# valves_card.net
KiCad netlist of a schematic drawn in EAGLE
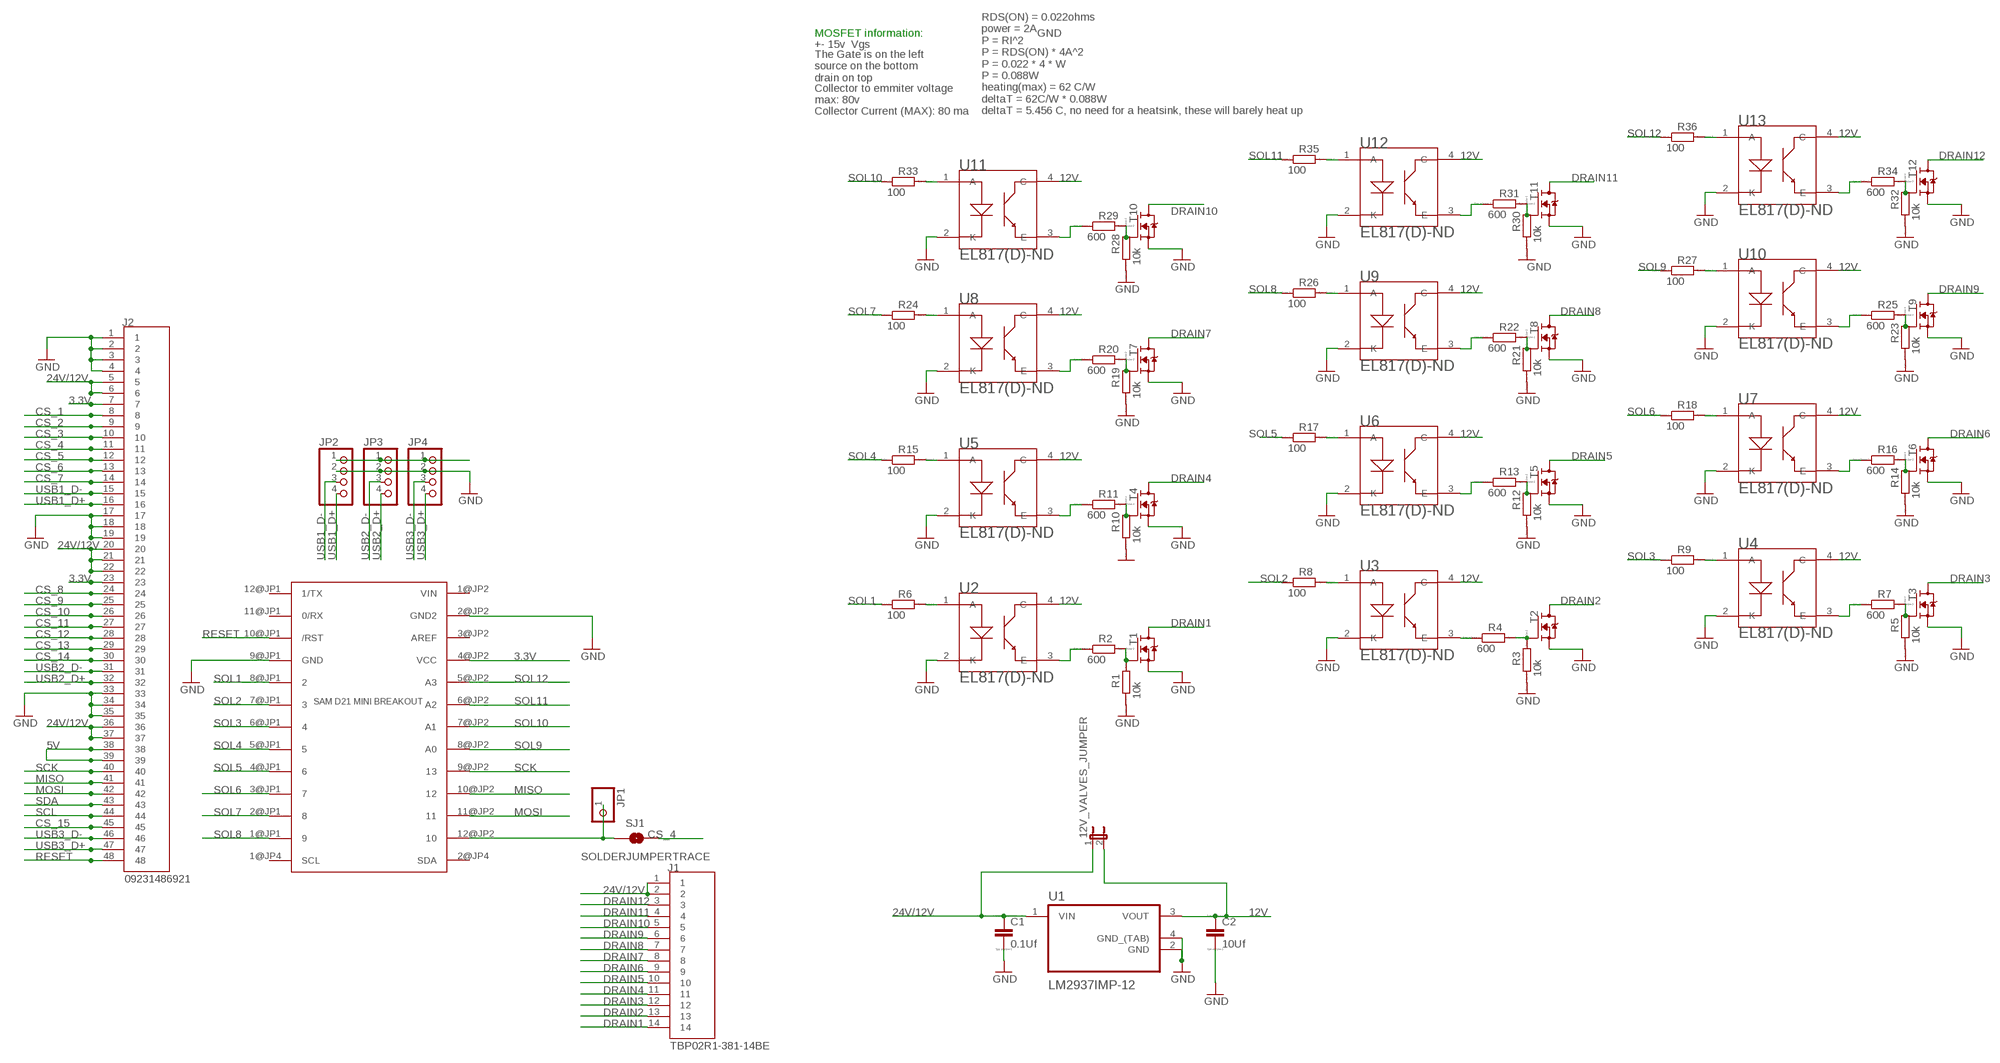
[diagram p0: schematic, sheet 1]

(export (version "E")
  (design (tool "Eeschema 10.0.6"))
  (components
    (comp (ref "12V_VALVES_JUMPER")
      (value "JUMPER-2SMD-NO")
      (footprint "eagle-import:SJ_2S-NO")
      (libsource (lib "eagle-import") (part "JUMPER-2SMD-NO"))
    )
    (comp (ref "C1")
      (value "0.1Uf")
      (footprint "eagle-import:C0805")
      (libsource (lib "eagle-import") (part "C"))
    )
    (comp (ref "C2")
      (value "10Uf")
      (footprint "eagle-import:C1206")
      (libsource (lib "eagle-import") (part "CC1206"))
    )
    (comp (ref "J1")
      (value "TBP02R1-381-14BE")
      (footprint "eagle-import:CUI_TBP02R1-381-14BE")
      (fields (field (name "MF") "CUI Devices"))
      (libsource (lib "eagle-import") (part "TBP02R1-381-14BE"))
    )
    (comp (ref "J2")
      (value "09231486921")
      (footprint "eagle-import:HARTING_09231486921")
      (fields (field (name "MF") "HARTING"))
      (libsource (lib "eagle-import") (part "09231486921"))
    )
    (comp (ref "JP1")
      (value "PINHD-1X1")
      (footprint "eagle-import:1X01")
      (libsource (lib "eagle-import") (part "PINHD-1X1"))
    )
    (comp (ref "JP2")
      (value "PINHD-1X4")
      (footprint "eagle-import:1X04")
      (libsource (lib "eagle-import") (part "PINHD-1X4"))
    )
    (comp (ref "JP3")
      (value "PINHD-1X4")
      (footprint "eagle-import:1X04")
      (libsource (lib "eagle-import") (part "PINHD-1X4"))
    )
    (comp (ref "JP4")
      (value "PINHD-1X4")
      (footprint "eagle-import:1X04")
      (libsource (lib "eagle-import") (part "PINHD-1X4"))
    )
    (comp (ref "M2")
      (value "SAM_D21_MINI_BREAKOUT")
      (footprint "eagle-import:JP1_SPARKFUN-SAMD21-MINI-BREAKOUT-V10")
      (libsource (lib "eagle-import") (part "SAM_D21_MINI_BREAKOUT"))
    )
    (comp (ref "R1")
      (value "10k")
      (footprint "eagle-import:R0805")
      (libsource (lib "eagle-import") (part "R"))
    )
    (comp (ref "R2")
      (value "600")
      (footprint "eagle-import:R0805")
      (libsource (lib "eagle-import") (part "R"))
    )
    (comp (ref "R3")
      (value "10k")
      (footprint "eagle-import:R0805")
      (libsource (lib "eagle-import") (part "R"))
    )
    (comp (ref "R4")
      (value "600")
      (footprint "eagle-import:R0805")
      (libsource (lib "eagle-import") (part "R"))
    )
    (comp (ref "R5")
      (value "10k")
      (footprint "eagle-import:R0805")
      (libsource (lib "eagle-import") (part "R"))
    )
    (comp (ref "R6")
      (value "100")
      (footprint "eagle-import:R0805")
      (libsource (lib "eagle-import") (part "R"))
    )
    (comp (ref "R7")
      (value "600")
      (footprint "eagle-import:R0805")
      (libsource (lib "eagle-import") (part "R"))
    )
    (comp (ref "R8")
      (value "100")
      (footprint "eagle-import:R0805")
      (libsource (lib "eagle-import") (part "R"))
    )
    (comp (ref "R9")
      (value "100")
      (footprint "eagle-import:R0805")
      (libsource (lib "eagle-import") (part "R"))
    )
    (comp (ref "R10")
      (value "10k")
      (footprint "eagle-import:R0805")
      (libsource (lib "eagle-import") (part "R"))
    )
    (comp (ref "R11")
      (value "600")
      (footprint "eagle-import:R0805")
      (libsource (lib "eagle-import") (part "R"))
    )
    (comp (ref "R12")
      (value "10k")
      (footprint "eagle-import:R0805")
      (libsource (lib "eagle-import") (part "R"))
    )
    (comp (ref "R13")
      (value "600")
      (footprint "eagle-import:R0805")
      (libsource (lib "eagle-import") (part "R"))
    )
    (comp (ref "R14")
      (value "10k")
      (footprint "eagle-import:R0805")
      (libsource (lib "eagle-import") (part "R"))
    )
    (comp (ref "R15")
      (value "100")
      (footprint "eagle-import:R0805")
      (libsource (lib "eagle-import") (part "R"))
    )
    (comp (ref "R16")
      (value "600")
      (footprint "eagle-import:R0805")
      (libsource (lib "eagle-import") (part "R"))
    )
    (comp (ref "R17")
      (value "100")
      (footprint "eagle-import:R0805")
      (libsource (lib "eagle-import") (part "R"))
    )
    (comp (ref "R18")
      (value "100")
      (footprint "eagle-import:R0805")
      (libsource (lib "eagle-import") (part "R"))
    )
    (comp (ref "R19")
      (value "10k")
      (footprint "eagle-import:R0805")
      (libsource (lib "eagle-import") (part "R"))
    )
    (comp (ref "R20")
      (value "600")
      (footprint "eagle-import:R0805")
      (libsource (lib "eagle-import") (part "R"))
    )
    (comp (ref "R21")
      (value "10k")
      (footprint "eagle-import:R0805")
      (libsource (lib "eagle-import") (part "R"))
    )
    (comp (ref "R22")
      (value "600")
      (footprint "eagle-import:R0805")
      (libsource (lib "eagle-import") (part "R"))
    )
    (comp (ref "R23")
      (value "10k")
      (footprint "eagle-import:R0805")
      (libsource (lib "eagle-import") (part "R"))
    )
    (comp (ref "R24")
      (value "100")
      (footprint "eagle-import:R0805")
      (libsource (lib "eagle-import") (part "R"))
    )
    (comp (ref "R25")
      (value "600")
      (footprint "eagle-import:R0805")
      (libsource (lib "eagle-import") (part "R"))
    )
    (comp (ref "R26")
      (value "100")
      (footprint "eagle-import:R0805")
      (libsource (lib "eagle-import") (part "R"))
    )
    (comp (ref "R27")
      (value "100")
      (footprint "eagle-import:R0805")
      (libsource (lib "eagle-import") (part "R"))
    )
    (comp (ref "R28")
      (value "10k")
      (footprint "eagle-import:R0805")
      (libsource (lib "eagle-import") (part "R"))
    )
    (comp (ref "R29")
      (value "600")
      (footprint "eagle-import:R0805")
      (libsource (lib "eagle-import") (part "R"))
    )
    (comp (ref "R30")
      (value "10k")
      (footprint "eagle-import:R0805")
      (libsource (lib "eagle-import") (part "R"))
    )
    (comp (ref "R31")
      (value "600")
      (footprint "eagle-import:R0805")
      (libsource (lib "eagle-import") (part "R"))
    )
    (comp (ref "R32")
      (value "10k")
      (footprint "eagle-import:R0805")
      (libsource (lib "eagle-import") (part "R"))
    )
    (comp (ref "R33")
      (value "100")
      (footprint "eagle-import:R0805")
      (libsource (lib "eagle-import") (part "R"))
    )
    (comp (ref "R34")
      (value "600")
      (footprint "eagle-import:R0805")
      (libsource (lib "eagle-import") (part "R"))
    )
    (comp (ref "R35")
      (value "100")
      (footprint "eagle-import:R0805")
      (libsource (lib "eagle-import") (part "R"))
    )
    (comp (ref "R36")
      (value "100")
      (footprint "eagle-import:R0805")
      (libsource (lib "eagle-import") (part "R"))
    )
    (comp (ref "SJ1")
      (value "SOLDERJUMPERTRACE")
      (footprint "eagle-import:SJ_2S-TRACE")
      (libsource (lib "eagle-import") (part "SOLDERJUMPERTRACE"))
    )
    (comp (ref "T1")
      (value "IRLZ44NSTRLPBF")
      (footprint "eagle-import:DPAK_TO252")
      (libsource (lib "eagle-import") (part "BUK9214-30A-118-DPAK"))
    )
    (comp (ref "T2")
      (value "IRLZ44NSTRLPBF")
      (footprint "eagle-import:DPAK_TO252")
      (libsource (lib "eagle-import") (part "BUK9214-30A-118-DPAK"))
    )
    (comp (ref "T3")
      (value "IRLZ44NSTRLPBF")
      (footprint "eagle-import:DPAK_TO252")
      (libsource (lib "eagle-import") (part "BUK9214-30A-118-DPAK"))
    )
    (comp (ref "T4")
      (value "IRLZ44NSTRLPBF")
      (footprint "eagle-import:DPAK_TO252")
      (libsource (lib "eagle-import") (part "BUK9214-30A-118-DPAK"))
    )
    (comp (ref "T5")
      (value "IRLZ44NSTRLPBF")
      (footprint "eagle-import:DPAK_TO252")
      (libsource (lib "eagle-import") (part "BUK9214-30A-118-DPAK"))
    )
    (comp (ref "T6")
      (value "IRLZ44NSTRLPBF")
      (footprint "eagle-import:DPAK_TO252")
      (libsource (lib "eagle-import") (part "BUK9214-30A-118-DPAK"))
    )
    (comp (ref "T7")
      (value "IRLZ44NSTRLPBF")
      (footprint "eagle-import:DPAK_TO252")
      (libsource (lib "eagle-import") (part "BUK9214-30A-118-DPAK"))
    )
    (comp (ref "T8")
      (value "IRLZ44NSTRLPBF")
      (footprint "eagle-import:DPAK_TO252")
      (libsource (lib "eagle-import") (part "BUK9214-30A-118-DPAK"))
    )
    (comp (ref "T9")
      (value "IRLZ44NSTRLPBF")
      (footprint "eagle-import:DPAK_TO252")
      (libsource (lib "eagle-import") (part "BUK9214-30A-118-DPAK"))
    )
    (comp (ref "T10")
      (value "IRLZ44NSTRLPBF")
      (footprint "eagle-import:DPAK_TO252")
      (libsource (lib "eagle-import") (part "BUK9214-30A-118-DPAK"))
    )
    (comp (ref "T11")
      (value "IRLZ44NSTRLPBF")
      (footprint "eagle-import:DPAK_TO252")
      (libsource (lib "eagle-import") (part "BUK9214-30A-118-DPAK"))
    )
    (comp (ref "T12")
      (value "IRLZ44NSTRLPBF")
      (footprint "eagle-import:DPAK_TO252")
      (libsource (lib "eagle-import") (part "BUK9214-30A-118-DPAK"))
    )
    (comp (ref "U1")
      (value "LM2937IMP-12")
      (footprint "eagle-import:SOT230P700X180-4N")
      (fields (field (name "MF") "Texas Instruments") (field (name "MP") "LM2937IMP-10"))
      (libsource (lib "eagle-import") (part "LM2937IMP-10"))
    )
    (comp (ref "U2")
      (value "EL817(D)-ND")
      (footprint "eagle-import:DIP762W25P254L650H453Q4B")
      (fields (field (name "MF") "Everlight") (field (name "MP") "EL817(C)") (field (name "MP_1") "OR-815"))
      (libsource (lib "eagle-import") (part "EL817C"))
    )
    (comp (ref "U3")
      (value "EL817(D)-ND")
      (footprint "eagle-import:DIP762W25P254L650H453Q4B")
      (fields (field (name "MF") "Everlight") (field (name "MP") "EL817(C)") (field (name "MP_1") "OR-815"))
      (libsource (lib "eagle-import") (part "EL817C"))
    )
    (comp (ref "U4")
      (value "EL817(D)-ND")
      (footprint "eagle-import:DIP762W25P254L650H453Q4B")
      (fields (field (name "MF") "Everlight") (field (name "MP") "EL817(C)"))
      (libsource (lib "eagle-import") (part "EL817C"))
    )
    (comp (ref "U5")
      (value "EL817(D)-ND")
      (footprint "eagle-import:DIP762W25P254L650H453Q4B")
      (fields (field (name "MF") "Everlight") (field (name "MP") "EL817(C)"))
      (libsource (lib "eagle-import") (part "EL817C"))
    )
    (comp (ref "U6")
      (value "EL817(D)-ND")
      (footprint "eagle-import:DIP762W25P254L650H453Q4B")
      (fields (field (name "MF") "Everlight") (field (name "MP") "EL817(C)"))
      (libsource (lib "eagle-import") (part "EL817C"))
    )
    (comp (ref "U7")
      (value "EL817(D)-ND")
      (footprint "eagle-import:DIP762W25P254L650H453Q4B")
      (fields (field (name "MF") "Everlight") (field (name "MP") "EL817(C)"))
      (libsource (lib "eagle-import") (part "EL817C"))
    )
    (comp (ref "U8")
      (value "EL817(D)-ND")
      (footprint "eagle-import:DIP762W25P254L650H453Q4B")
      (fields (field (name "MF") "Everlight") (field (name "MP") "EL817(C)"))
      (libsource (lib "eagle-import") (part "EL817C"))
    )
    (comp (ref "U9")
      (value "EL817(D)-ND")
      (footprint "eagle-import:DIP762W25P254L650H453Q4B")
      (fields (field (name "MF") "Everlight") (field (name "MP") "EL817(C)"))
      (libsource (lib "eagle-import") (part "EL817C"))
    )
    (comp (ref "U10")
      (value "EL817(D)-ND")
      (footprint "eagle-import:DIP762W25P254L650H453Q4B")
      (fields (field (name "MF") "Everlight") (field (name "MP") "EL817(C)"))
      (libsource (lib "eagle-import") (part "EL817C"))
    )
    (comp (ref "U11")
      (value "EL817(D)-ND")
      (footprint "eagle-import:DIP762W25P254L650H453Q4B")
      (fields (field (name "MF") "Everlight") (field (name "MP") "EL817(C)"))
      (libsource (lib "eagle-import") (part "EL817C"))
    )
    (comp (ref "U12")
      (value "EL817(D)-ND")
      (footprint "eagle-import:DIP762W25P254L650H453Q4B")
      (fields (field (name "MF") "Everlight") (field (name "MP") "EL817(C)"))
      (libsource (lib "eagle-import") (part "EL817C"))
    )
    (comp (ref "U13")
      (value "EL817(D)-ND")
      (footprint "eagle-import:DIP762W25P254L650H453Q4B")
      (fields (field (name "MF") "Everlight") (field (name "MP") "EL817(C)"))
      (libsource (lib "eagle-import") (part "EL817C"))
    )
  )
  (nets
    (net (code "1") (name "/3.3V") (class "Default")
      (node (ref "J2") (pin "23") (pinfunction "23_23") (pintype "passive"))
      (node (ref "J2") (pin "7") (pinfunction "7_7") (pintype "passive"))
      (node (ref "M2") (pin "4@JP2") (pinfunction "VCC_4@JP2") (pintype "power_in"))
    )
    (net (code "2") (name "/5V") (class "Default")
      (node (ref "J2") (pin "38") (pinfunction "38_38") (pintype "passive"))
      (node (ref "J2") (pin "39") (pinfunction "39_39") (pintype "passive"))
      (node (ref "JP2") (pin "1") (pinfunction "1_1") (pintype "passive"))
      (node (ref "JP3") (pin "1") (pinfunction "1_1") (pintype "passive"))
      (node (ref "JP4") (pin "1") (pinfunction "1_1") (pintype "passive"))
    )
    (net (code "3") (name "/12V") (class "Default")
      (node (ref "12V_VALVES_JUMPER") (pin "2") (pinfunction "2_2") (pintype "passive"))
      (node (ref "C2") (pin "1") (pinfunction "1_1") (pintype "passive"))
      (node (ref "U1") (pin "3") (pinfunction "VOUT_3") (pintype "output"))
      (node (ref "U10") (pin "4") (pinfunction "C_4") (pintype "passive"))
      (node (ref "U11") (pin "4") (pinfunction "C_4") (pintype "passive"))
      (node (ref "U12") (pin "4") (pinfunction "C_4") (pintype "passive"))
      (node (ref "U13") (pin "4") (pinfunction "C_4") (pintype "passive"))
      (node (ref "U2") (pin "4") (pinfunction "C_4") (pintype "passive"))
      (node (ref "U3") (pin "4") (pinfunction "C_4") (pintype "passive"))
      (node (ref "U4") (pin "4") (pinfunction "C_4") (pintype "passive"))
      (node (ref "U5") (pin "4") (pinfunction "C_4") (pintype "passive"))
      (node (ref "U6") (pin "4") (pinfunction "C_4") (pintype "passive"))
      (node (ref "U7") (pin "4") (pinfunction "C_4") (pintype "passive"))
      (node (ref "U8") (pin "4") (pinfunction "C_4") (pintype "passive"))
      (node (ref "U9") (pin "4") (pinfunction "C_4") (pintype "passive"))
    )
    (net (code "4") (name "/24V{slash}12V") (class "Default")
      (node (ref "12V_VALVES_JUMPER") (pin "1") (pinfunction "1_1") (pintype "passive"))
      (node (ref "C1") (pin "1") (pinfunction "1_1") (pintype "passive"))
      (node (ref "J1") (pin "1") (pinfunction "1_1") (pintype "passive"))
      (node (ref "J1") (pin "2") (pinfunction "2_2") (pintype "passive"))
      (node (ref "J2") (pin "20") (pinfunction "20_20") (pintype "passive"))
      (node (ref "J2") (pin "21") (pinfunction "21_21") (pintype "passive"))
      (node (ref "J2") (pin "22") (pinfunction "22_22") (pintype "passive"))
      (node (ref "J2") (pin "36") (pinfunction "36_36") (pintype "passive"))
      (node (ref "J2") (pin "37") (pinfunction "37_37") (pintype "passive"))
      (node (ref "J2") (pin "5") (pinfunction "5_5") (pintype "passive"))
      (node (ref "J2") (pin "6") (pinfunction "6_6") (pintype "passive"))
      (node (ref "U1") (pin "1") (pinfunction "VIN_1") (pintype "input"))
    )
    (net (code "5") (name "/AREF") (class "Default")
      (node (ref "M2") (pin "3@JP2") (pinfunction "AREF_3@JP2") (pintype "power_in"))
    )
    (net (code "6") (name "/CS_1") (class "Default")
      (node (ref "J2") (pin "8") (pinfunction "8_8") (pintype "passive"))
    )
    (net (code "7") (name "/CS_2") (class "Default")
      (node (ref "J2") (pin "9") (pinfunction "9_9") (pintype "passive"))
    )
    (net (code "8") (name "/CS_3") (class "Default")
      (node (ref "J2") (pin "10") (pinfunction "10_10") (pintype "passive"))
    )
    (net (code "9") (name "/CS_4") (class "Default")
      (node (ref "J2") (pin "11") (pinfunction "11_11") (pintype "passive"))
      (node (ref "SJ1") (pin "2") (pinfunction "2_2") (pintype "passive"))
    )
    (net (code "10") (name "/CS_5") (class "Default")
      (node (ref "J2") (pin "12") (pinfunction "12_12") (pintype "passive"))
    )
    (net (code "11") (name "/CS_6") (class "Default")
      (node (ref "J2") (pin "13") (pinfunction "13_13") (pintype "passive"))
    )
    (net (code "12") (name "/CS_7") (class "Default")
      (node (ref "J2") (pin "14") (pinfunction "14_14") (pintype "passive"))
    )
    (net (code "13") (name "/CS_8") (class "Default")
      (node (ref "J2") (pin "24") (pinfunction "24_24") (pintype "passive"))
    )
    (net (code "14") (name "/CS_9") (class "Default")
      (node (ref "J2") (pin "25") (pinfunction "25_25") (pintype "passive"))
    )
    (net (code "15") (name "/CS_10") (class "Default")
      (node (ref "J2") (pin "26") (pinfunction "26_26") (pintype "passive"))
    )
    (net (code "16") (name "/CS_11") (class "Default")
      (node (ref "J2") (pin "27") (pinfunction "27_27") (pintype "passive"))
    )
    (net (code "17") (name "/CS_12") (class "Default")
      (node (ref "J2") (pin "28") (pinfunction "28_28") (pintype "passive"))
    )
    (net (code "18") (name "/CS_13") (class "Default")
      (node (ref "J2") (pin "29") (pinfunction "29_29") (pintype "passive"))
    )
    (net (code "19") (name "/CS_14") (class "Default")
      (node (ref "J2") (pin "30") (pinfunction "30_30") (pintype "passive"))
    )
    (net (code "20") (name "/CS_15") (class "Default")
      (node (ref "J2") (pin "45") (pinfunction "45_45") (pintype "passive"))
    )
    (net (code "21") (name "/DRAIN1") (class "Default")
      (node (ref "J1") (pin "14") (pinfunction "14_14") (pintype "passive"))
      (node (ref "T1") (pin "2") (pinfunction "D_2") (pintype "passive"))
    )
    (net (code "22") (name "/DRAIN2") (class "Default")
      (node (ref "J1") (pin "13") (pinfunction "13_13") (pintype "passive"))
      (node (ref "T2") (pin "2") (pinfunction "D_2") (pintype "passive"))
    )
    (net (code "23") (name "/DRAIN3") (class "Default")
      (node (ref "J1") (pin "12") (pinfunction "12_12") (pintype "passive"))
      (node (ref "T3") (pin "2") (pinfunction "D_2") (pintype "passive"))
    )
    (net (code "24") (name "/DRAIN4") (class "Default")
      (node (ref "J1") (pin "11") (pinfunction "11_11") (pintype "passive"))
      (node (ref "T4") (pin "2") (pinfunction "D_2") (pintype "passive"))
    )
    (net (code "25") (name "/DRAIN5") (class "Default")
      (node (ref "J1") (pin "10") (pinfunction "10_10") (pintype "passive"))
      (node (ref "T5") (pin "2") (pinfunction "D_2") (pintype "passive"))
    )
    (net (code "26") (name "/DRAIN6") (class "Default")
      (node (ref "J1") (pin "9") (pinfunction "9_9") (pintype "passive"))
      (node (ref "T6") (pin "2") (pinfunction "D_2") (pintype "passive"))
    )
    (net (code "27") (name "/DRAIN7") (class "Default")
      (node (ref "J1") (pin "8") (pinfunction "8_8") (pintype "passive"))
      (node (ref "T7") (pin "2") (pinfunction "D_2") (pintype "passive"))
    )
    (net (code "28") (name "/DRAIN8") (class "Default")
      (node (ref "J1") (pin "7") (pinfunction "7_7") (pintype "passive"))
      (node (ref "T8") (pin "2") (pinfunction "D_2") (pintype "passive"))
    )
    (net (code "29") (name "/DRAIN9") (class "Default")
      (node (ref "J1") (pin "6") (pinfunction "6_6") (pintype "passive"))
      (node (ref "T9") (pin "2") (pinfunction "D_2") (pintype "passive"))
    )
    (net (code "30") (name "/DRAIN10") (class "Default")
      (node (ref "J1") (pin "5") (pinfunction "5_5") (pintype "passive"))
      (node (ref "T10") (pin "2") (pinfunction "D_2") (pintype "passive"))
    )
    (net (code "31") (name "/DRAIN11") (class "Default")
      (node (ref "J1") (pin "4") (pinfunction "4_4") (pintype "passive"))
      (node (ref "T11") (pin "2") (pinfunction "D_2") (pintype "passive"))
    )
    (net (code "32") (name "/DRAIN12") (class "Default")
      (node (ref "J1") (pin "3") (pinfunction "3_3") (pintype "passive"))
      (node (ref "T12") (pin "2") (pinfunction "D_2") (pintype "passive"))
    )
    (net (code "33") (name "/MISO") (class "Default")
      (node (ref "J2") (pin "41") (pinfunction "41_41") (pintype "passive"))
      (node (ref "M2") (pin "10@JP2") (pinfunction "12_10@JP2") (pintype "bidirectional"))
    )
    (net (code "34") (name "/MOSI") (class "Default")
      (node (ref "J2") (pin "42") (pinfunction "42_42") (pintype "passive"))
      (node (ref "M2") (pin "11@JP2") (pinfunction "11_11@JP2") (pintype "bidirectional"))
    )
    (net (code "35") (name "/RESET") (class "Default")
      (node (ref "J2") (pin "48") (pinfunction "48_48") (pintype "passive"))
      (node (ref "M2") (pin "10@JP1") (pinfunction "/RST_10@JP1") (pintype "input"))
    )
    (net (code "36") (name "/SCK") (class "Default")
      (node (ref "J2") (pin "40") (pinfunction "40_40") (pintype "passive"))
      (node (ref "M2") (pin "9@JP2") (pinfunction "13_9@JP2") (pintype "bidirectional"))
    )
    (net (code "37") (name "/SCL") (class "Default")
      (node (ref "J2") (pin "44") (pinfunction "44_44") (pintype "passive"))
    )
    (net (code "38") (name "/SDA") (class "Default")
      (node (ref "J2") (pin "43") (pinfunction "43_43") (pintype "passive"))
    )
    (net (code "39") (name "/SOL1") (class "Default")
      (node (ref "M2") (pin "8@JP1") (pinfunction "2_8@JP1") (pintype "bidirectional"))
      (node (ref "R6") (pin "1") (pinfunction "1_1") (pintype "passive"))
    )
    (net (code "40") (name "/SOL2") (class "Default")
      (node (ref "M2") (pin "7@JP1") (pinfunction "3_7@JP1") (pintype "bidirectional"))
      (node (ref "R8") (pin "1") (pinfunction "1_1") (pintype "passive"))
    )
    (net (code "41") (name "/SOL3") (class "Default")
      (node (ref "M2") (pin "6@JP1") (pinfunction "4_6@JP1") (pintype "bidirectional"))
      (node (ref "R9") (pin "1") (pinfunction "1_1") (pintype "passive"))
    )
    (net (code "42") (name "/SOL4") (class "Default")
      (node (ref "M2") (pin "5@JP1") (pinfunction "5_5@JP1") (pintype "bidirectional"))
      (node (ref "R15") (pin "1") (pinfunction "1_1") (pintype "passive"))
    )
    (net (code "43") (name "/SOL5") (class "Default")
      (node (ref "M2") (pin "4@JP1") (pinfunction "6_4@JP1") (pintype "bidirectional"))
      (node (ref "R17") (pin "1") (pinfunction "1_1") (pintype "passive"))
    )
    (net (code "44") (name "/SOL6") (class "Default")
      (node (ref "M2") (pin "3@JP1") (pinfunction "7_3@JP1") (pintype "bidirectional"))
      (node (ref "R18") (pin "1") (pinfunction "1_1") (pintype "passive"))
    )
    (net (code "45") (name "/SOL7") (class "Default")
      (node (ref "M2") (pin "2@JP1") (pinfunction "8_2@JP1") (pintype "bidirectional"))
      (node (ref "R24") (pin "1") (pinfunction "1_1") (pintype "passive"))
    )
    (net (code "46") (name "/SOL8") (class "Default")
      (node (ref "M2") (pin "1@JP1") (pinfunction "9_1@JP1") (pintype "bidirectional"))
      (node (ref "R26") (pin "1") (pinfunction "1_1") (pintype "passive"))
    )
    (net (code "47") (name "/SOL9") (class "Default")
      (node (ref "M2") (pin "8@JP2") (pinfunction "A0_8@JP2") (pintype "bidirectional"))
      (node (ref "R27") (pin "1") (pinfunction "1_1") (pintype "passive"))
    )
    (net (code "48") (name "/SOL10") (class "Default")
      (node (ref "M2") (pin "7@JP2") (pinfunction "A1_7@JP2") (pintype "bidirectional"))
      (node (ref "R33") (pin "1") (pinfunction "1_1") (pintype "passive"))
    )
    (net (code "49") (name "/SOL11") (class "Default")
      (node (ref "M2") (pin "6@JP2") (pinfunction "A2_6@JP2") (pintype "bidirectional"))
      (node (ref "R35") (pin "1") (pinfunction "1_1") (pintype "passive"))
    )
    (net (code "50") (name "/SOL12") (class "Default")
      (node (ref "M2") (pin "5@JP2") (pinfunction "A3_5@JP2") (pintype "bidirectional"))
      (node (ref "R36") (pin "1") (pinfunction "1_1") (pintype "passive"))
    )
    (net (code "51") (name "/USB1_D+") (class "Default")
      (node (ref "J2") (pin "16") (pinfunction "16_16") (pintype "passive"))
      (node (ref "JP2") (pin "4") (pinfunction "4_4") (pintype "passive"))
    )
    (net (code "52") (name "/USB1_D-") (class "Default")
      (node (ref "J2") (pin "15") (pinfunction "15_15") (pintype "passive"))
      (node (ref "JP2") (pin "3") (pinfunction "3_3") (pintype "passive"))
    )
    (net (code "53") (name "/USB2_D+") (class "Default")
      (node (ref "J2") (pin "32") (pinfunction "32_32") (pintype "passive"))
      (node (ref "JP3") (pin "4") (pinfunction "4_4") (pintype "passive"))
    )
    (net (code "54") (name "/USB2_D-") (class "Default")
      (node (ref "J2") (pin "31") (pinfunction "31_31") (pintype "passive"))
      (node (ref "JP3") (pin "3") (pinfunction "3_3") (pintype "passive"))
    )
    (net (code "55") (name "/USB3_D+") (class "Default")
      (node (ref "J2") (pin "47") (pinfunction "47_47") (pintype "passive"))
      (node (ref "JP4") (pin "4") (pinfunction "4_4") (pintype "passive"))
    )
    (net (code "56") (name "/USB3_D-") (class "Default")
      (node (ref "J2") (pin "46") (pinfunction "46_46") (pintype "passive"))
      (node (ref "JP4") (pin "3") (pinfunction "3_3") (pintype "passive"))
    )
    (net (code "57") (name "/VIN") (class "Default")
      (node (ref "M2") (pin "1@JP2") (pinfunction "VIN_1@JP2") (pintype "power_in"))
    )
    (net (code "58") (name "GND") (class "Default")
      (node (ref "C1") (pin "2") (pinfunction "2_2") (pintype "passive"))
      (node (ref "C2") (pin "2") (pinfunction "2_2") (pintype "passive"))
      (node (ref "J2") (pin "1") (pinfunction "1_1") (pintype "passive"))
      (node (ref "J2") (pin "17") (pinfunction "17_17") (pintype "passive"))
      (node (ref "J2") (pin "18") (pinfunction "18_18") (pintype "passive"))
      (node (ref "J2") (pin "19") (pinfunction "19_19") (pintype "passive"))
      (node (ref "J2") (pin "2") (pinfunction "2_2") (pintype "passive"))
      (node (ref "J2") (pin "3") (pinfunction "3_3") (pintype "passive"))
      (node (ref "J2") (pin "33") (pinfunction "33_33") (pintype "passive"))
      (node (ref "J2") (pin "34") (pinfunction "34_34") (pintype "passive"))
      (node (ref "J2") (pin "35") (pinfunction "35_35") (pintype "passive"))
      (node (ref "J2") (pin "4") (pinfunction "4_4") (pintype "passive"))
      (node (ref "JP2") (pin "2") (pinfunction "2_2") (pintype "passive"))
      (node (ref "JP3") (pin "2") (pinfunction "2_2") (pintype "passive"))
      (node (ref "JP4") (pin "2") (pinfunction "2_2") (pintype "passive"))
      (node (ref "M2") (pin "2@JP2") (pinfunction "GND2_2@JP2") (pintype "power_in"))
      (node (ref "M2") (pin "9@JP1") (pinfunction "GND_9@JP1") (pintype "power_in"))
      (node (ref "R1") (pin "1") (pinfunction "1_1") (pintype "passive"))
      (node (ref "R10") (pin "1") (pinfunction "1_1") (pintype "passive"))
      (node (ref "R12") (pin "1") (pinfunction "1_1") (pintype "passive"))
      (node (ref "R14") (pin "1") (pinfunction "1_1") (pintype "passive"))
      (node (ref "R19") (pin "1") (pinfunction "1_1") (pintype "passive"))
      (node (ref "R21") (pin "1") (pinfunction "1_1") (pintype "passive"))
      (node (ref "R23") (pin "1") (pinfunction "1_1") (pintype "passive"))
      (node (ref "R28") (pin "1") (pinfunction "1_1") (pintype "passive"))
      (node (ref "R3") (pin "1") (pinfunction "1_1") (pintype "passive"))
      (node (ref "R30") (pin "1") (pinfunction "1_1") (pintype "passive"))
      (node (ref "R32") (pin "1") (pinfunction "1_1") (pintype "passive"))
      (node (ref "R5") (pin "1") (pinfunction "1_1") (pintype "passive"))
      (node (ref "T1") (pin "3") (pinfunction "S_3") (pintype "passive"))
      (node (ref "T10") (pin "3") (pinfunction "S_3") (pintype "passive"))
      (node (ref "T11") (pin "3") (pinfunction "S_3") (pintype "passive"))
      (node (ref "T12") (pin "3") (pinfunction "S_3") (pintype "passive"))
      (node (ref "T2") (pin "3") (pinfunction "S_3") (pintype "passive"))
      (node (ref "T3") (pin "3") (pinfunction "S_3") (pintype "passive"))
      (node (ref "T4") (pin "3") (pinfunction "S_3") (pintype "passive"))
      (node (ref "T5") (pin "3") (pinfunction "S_3") (pintype "passive"))
      (node (ref "T6") (pin "3") (pinfunction "S_3") (pintype "passive"))
      (node (ref "T7") (pin "3") (pinfunction "S_3") (pintype "passive"))
      (node (ref "T8") (pin "3") (pinfunction "S_3") (pintype "passive"))
      (node (ref "T9") (pin "3") (pinfunction "S_3") (pintype "passive"))
      (node (ref "U1") (pin "2") (pinfunction "GND_2") (pintype "power_in"))
      (node (ref "U1") (pin "4") (pinfunction "GND_(TAB)_4") (pintype "power_in"))
      (node (ref "U10") (pin "2") (pinfunction "K_2") (pintype "passive"))
      (node (ref "U11") (pin "2") (pinfunction "K_2") (pintype "passive"))
      (node (ref "U12") (pin "2") (pinfunction "K_2") (pintype "passive"))
      (node (ref "U13") (pin "2") (pinfunction "K_2") (pintype "passive"))
      (node (ref "U2") (pin "2") (pinfunction "K_2") (pintype "passive"))
      (node (ref "U3") (pin "2") (pinfunction "K_2") (pintype "passive"))
      (node (ref "U4") (pin "2") (pinfunction "K_2") (pintype "passive"))
      (node (ref "U5") (pin "2") (pinfunction "K_2") (pintype "passive"))
      (node (ref "U6") (pin "2") (pinfunction "K_2") (pintype "passive"))
      (node (ref "U7") (pin "2") (pinfunction "K_2") (pintype "passive"))
      (node (ref "U8") (pin "2") (pinfunction "K_2") (pintype "passive"))
      (node (ref "U9") (pin "2") (pinfunction "K_2") (pintype "passive"))
    )
    (net (code "59") (name "Net-(M2-10)") (class "Default")
      (node (ref "JP1") (pin "1") (pinfunction "1_1") (pintype "passive"))
      (node (ref "M2") (pin "12@JP2") (pinfunction "10_12@JP2") (pintype "bidirectional"))
      (node (ref "SJ1") (pin "1") (pinfunction "1_1") (pintype "passive"))
    )
    (net (code "60") (name "Net-(T1-G)") (class "Default")
      (node (ref "R1") (pin "2") (pinfunction "2_2") (pintype "passive"))
      (node (ref "R2") (pin "2") (pinfunction "2_2") (pintype "passive"))
      (node (ref "T1") (pin "1") (pinfunction "G_1") (pintype "passive"))
    )
    (net (code "61") (name "Net-(T2-G)") (class "Default")
      (node (ref "R3") (pin "2") (pinfunction "2_2") (pintype "passive"))
      (node (ref "R4") (pin "2") (pinfunction "2_2") (pintype "passive"))
      (node (ref "T2") (pin "1") (pinfunction "G_1") (pintype "passive"))
    )
    (net (code "62") (name "Net-(T3-G)") (class "Default")
      (node (ref "R5") (pin "2") (pinfunction "2_2") (pintype "passive"))
      (node (ref "R7") (pin "2") (pinfunction "2_2") (pintype "passive"))
      (node (ref "T3") (pin "1") (pinfunction "G_1") (pintype "passive"))
    )
    (net (code "63") (name "Net-(T4-G)") (class "Default")
      (node (ref "R10") (pin "2") (pinfunction "2_2") (pintype "passive"))
      (node (ref "R11") (pin "2") (pinfunction "2_2") (pintype "passive"))
      (node (ref "T4") (pin "1") (pinfunction "G_1") (pintype "passive"))
    )
    (net (code "64") (name "Net-(T5-G)") (class "Default")
      (node (ref "R12") (pin "2") (pinfunction "2_2") (pintype "passive"))
      (node (ref "R13") (pin "2") (pinfunction "2_2") (pintype "passive"))
      (node (ref "T5") (pin "1") (pinfunction "G_1") (pintype "passive"))
    )
    (net (code "65") (name "Net-(T6-G)") (class "Default")
      (node (ref "R14") (pin "2") (pinfunction "2_2") (pintype "passive"))
      (node (ref "R16") (pin "2") (pinfunction "2_2") (pintype "passive"))
      (node (ref "T6") (pin "1") (pinfunction "G_1") (pintype "passive"))
    )
    (net (code "66") (name "Net-(T7-G)") (class "Default")
      (node (ref "R19") (pin "2") (pinfunction "2_2") (pintype "passive"))
      (node (ref "R20") (pin "2") (pinfunction "2_2") (pintype "passive"))
      (node (ref "T7") (pin "1") (pinfunction "G_1") (pintype "passive"))
    )
    (net (code "67") (name "Net-(T8-G)") (class "Default")
      (node (ref "R21") (pin "2") (pinfunction "2_2") (pintype "passive"))
      (node (ref "R22") (pin "2") (pinfunction "2_2") (pintype "passive"))
      (node (ref "T8") (pin "1") (pinfunction "G_1") (pintype "passive"))
    )
    (net (code "68") (name "Net-(T9-G)") (class "Default")
      (node (ref "R23") (pin "2") (pinfunction "2_2") (pintype "passive"))
      (node (ref "R25") (pin "2") (pinfunction "2_2") (pintype "passive"))
      (node (ref "T9") (pin "1") (pinfunction "G_1") (pintype "passive"))
    )
    (net (code "69") (name "Net-(T10-G)") (class "Default")
      (node (ref "R28") (pin "2") (pinfunction "2_2") (pintype "passive"))
      (node (ref "R29") (pin "2") (pinfunction "2_2") (pintype "passive"))
      (node (ref "T10") (pin "1") (pinfunction "G_1") (pintype "passive"))
    )
    (net (code "70") (name "Net-(T11-G)") (class "Default")
      (node (ref "R30") (pin "2") (pinfunction "2_2") (pintype "passive"))
      (node (ref "R31") (pin "2") (pinfunction "2_2") (pintype "passive"))
      (node (ref "T11") (pin "1") (pinfunction "G_1") (pintype "passive"))
    )
    (net (code "71") (name "Net-(T12-G)") (class "Default")
      (node (ref "R32") (pin "2") (pinfunction "2_2") (pintype "passive"))
      (node (ref "R34") (pin "2") (pinfunction "2_2") (pintype "passive"))
      (node (ref "T12") (pin "1") (pinfunction "G_1") (pintype "passive"))
    )
    (net (code "72") (name "Net-(U2-A)") (class "Default")
      (node (ref "R6") (pin "2") (pinfunction "2_2") (pintype "passive"))
      (node (ref "U2") (pin "1") (pinfunction "A_1") (pintype "passive"))
    )
    (net (code "73") (name "Net-(U2-E)") (class "Default")
      (node (ref "R2") (pin "1") (pinfunction "1_1") (pintype "passive"))
      (node (ref "U2") (pin "3") (pinfunction "E_3") (pintype "passive"))
    )
    (net (code "74") (name "Net-(U3-A)") (class "Default")
      (node (ref "R8") (pin "2") (pinfunction "2_2") (pintype "passive"))
      (node (ref "U3") (pin "1") (pinfunction "A_1") (pintype "passive"))
    )
    (net (code "75") (name "Net-(U3-E)") (class "Default")
      (node (ref "R4") (pin "1") (pinfunction "1_1") (pintype "passive"))
      (node (ref "U3") (pin "3") (pinfunction "E_3") (pintype "passive"))
    )
    (net (code "76") (name "Net-(U4-A)") (class "Default")
      (node (ref "R9") (pin "2") (pinfunction "2_2") (pintype "passive"))
      (node (ref "U4") (pin "1") (pinfunction "A_1") (pintype "passive"))
    )
    (net (code "77") (name "Net-(U4-E)") (class "Default")
      (node (ref "R7") (pin "1") (pinfunction "1_1") (pintype "passive"))
      (node (ref "U4") (pin "3") (pinfunction "E_3") (pintype "passive"))
    )
    (net (code "78") (name "Net-(U5-A)") (class "Default")
      (node (ref "R15") (pin "2") (pinfunction "2_2") (pintype "passive"))
      (node (ref "U5") (pin "1") (pinfunction "A_1") (pintype "passive"))
    )
    (net (code "79") (name "Net-(U5-E)") (class "Default")
      (node (ref "R11") (pin "1") (pinfunction "1_1") (pintype "passive"))
      (node (ref "U5") (pin "3") (pinfunction "E_3") (pintype "passive"))
    )
    (net (code "80") (name "Net-(U6-A)") (class "Default")
      (node (ref "R17") (pin "2") (pinfunction "2_2") (pintype "passive"))
      (node (ref "U6") (pin "1") (pinfunction "A_1") (pintype "passive"))
    )
    (net (code "81") (name "Net-(U6-E)") (class "Default")
      (node (ref "R13") (pin "1") (pinfunction "1_1") (pintype "passive"))
      (node (ref "U6") (pin "3") (pinfunction "E_3") (pintype "passive"))
    )
    (net (code "82") (name "Net-(U7-A)") (class "Default")
      (node (ref "R18") (pin "2") (pinfunction "2_2") (pintype "passive"))
      (node (ref "U7") (pin "1") (pinfunction "A_1") (pintype "passive"))
    )
    (net (code "83") (name "Net-(U7-E)") (class "Default")
      (node (ref "R16") (pin "1") (pinfunction "1_1") (pintype "passive"))
      (node (ref "U7") (pin "3") (pinfunction "E_3") (pintype "passive"))
    )
    (net (code "84") (name "Net-(U8-A)") (class "Default")
      (node (ref "R24") (pin "2") (pinfunction "2_2") (pintype "passive"))
      (node (ref "U8") (pin "1") (pinfunction "A_1") (pintype "passive"))
    )
    (net (code "85") (name "Net-(U8-E)") (class "Default")
      (node (ref "R20") (pin "1") (pinfunction "1_1") (pintype "passive"))
      (node (ref "U8") (pin "3") (pinfunction "E_3") (pintype "passive"))
    )
    (net (code "86") (name "Net-(U9-A)") (class "Default")
      (node (ref "R26") (pin "2") (pinfunction "2_2") (pintype "passive"))
      (node (ref "U9") (pin "1") (pinfunction "A_1") (pintype "passive"))
    )
    (net (code "87") (name "Net-(U9-E)") (class "Default")
      (node (ref "R22") (pin "1") (pinfunction "1_1") (pintype "passive"))
      (node (ref "U9") (pin "3") (pinfunction "E_3") (pintype "passive"))
    )
    (net (code "88") (name "Net-(U10-A)") (class "Default")
      (node (ref "R27") (pin "2") (pinfunction "2_2") (pintype "passive"))
      (node (ref "U10") (pin "1") (pinfunction "A_1") (pintype "passive"))
    )
    (net (code "89") (name "Net-(U10-E)") (class "Default")
      (node (ref "R25") (pin "1") (pinfunction "1_1") (pintype "passive"))
      (node (ref "U10") (pin "3") (pinfunction "E_3") (pintype "passive"))
    )
    (net (code "90") (name "Net-(U11-A)") (class "Default")
      (node (ref "R33") (pin "2") (pinfunction "2_2") (pintype "passive"))
      (node (ref "U11") (pin "1") (pinfunction "A_1") (pintype "passive"))
    )
    (net (code "91") (name "Net-(U11-E)") (class "Default")
      (node (ref "R29") (pin "1") (pinfunction "1_1") (pintype "passive"))
      (node (ref "U11") (pin "3") (pinfunction "E_3") (pintype "passive"))
    )
    (net (code "92") (name "Net-(U12-A)") (class "Default")
      (node (ref "R35") (pin "2") (pinfunction "2_2") (pintype "passive"))
      (node (ref "U12") (pin "1") (pinfunction "A_1") (pintype "passive"))
    )
    (net (code "93") (name "Net-(U12-E)") (class "Default")
      (node (ref "R31") (pin "1") (pinfunction "1_1") (pintype "passive"))
      (node (ref "U12") (pin "3") (pinfunction "E_3") (pintype "passive"))
    )
    (net (code "94") (name "Net-(U13-A)") (class "Default")
      (node (ref "R36") (pin "2") (pinfunction "2_2") (pintype "passive"))
      (node (ref "U13") (pin "1") (pinfunction "A_1") (pintype "passive"))
    )
    (net (code "95") (name "Net-(U13-E)") (class "Default")
      (node (ref "R34") (pin "1") (pinfunction "1_1") (pintype "passive"))
      (node (ref "U13") (pin "3") (pinfunction "E_3") (pintype "passive"))
    )
    (net (code "96") (name "unconnected-(M2-0{slash}RX-Pad11@JP1)") (class "Default")
      (node (ref "M2") (pin "11@JP1") (pinfunction "0/RX_11@JP1") (pintype "bidirectional"))
    )
    (net (code "97") (name "unconnected-(M2-1{slash}TX-Pad12@JP1)") (class "Default")
      (node (ref "M2") (pin "12@JP1") (pinfunction "1/TX_12@JP1") (pintype "bidirectional"))
    )
    (net (code "98") (name "unconnected-(M2-SCL-Pad1@JP4)") (class "Default")
      (node (ref "M2") (pin "1@JP4") (pinfunction "SCL_1@JP4") (pintype "bidirectional"))
    )
    (net (code "99") (name "unconnected-(M2-SDA-Pad2@JP4)") (class "Default")
      (node (ref "M2") (pin "2@JP4") (pinfunction "SDA_2@JP4") (pintype "bidirectional"))
    )
  )
)
